# urov_schematic_2.net
KiCad netlist of a schematic drawn in EAGLE
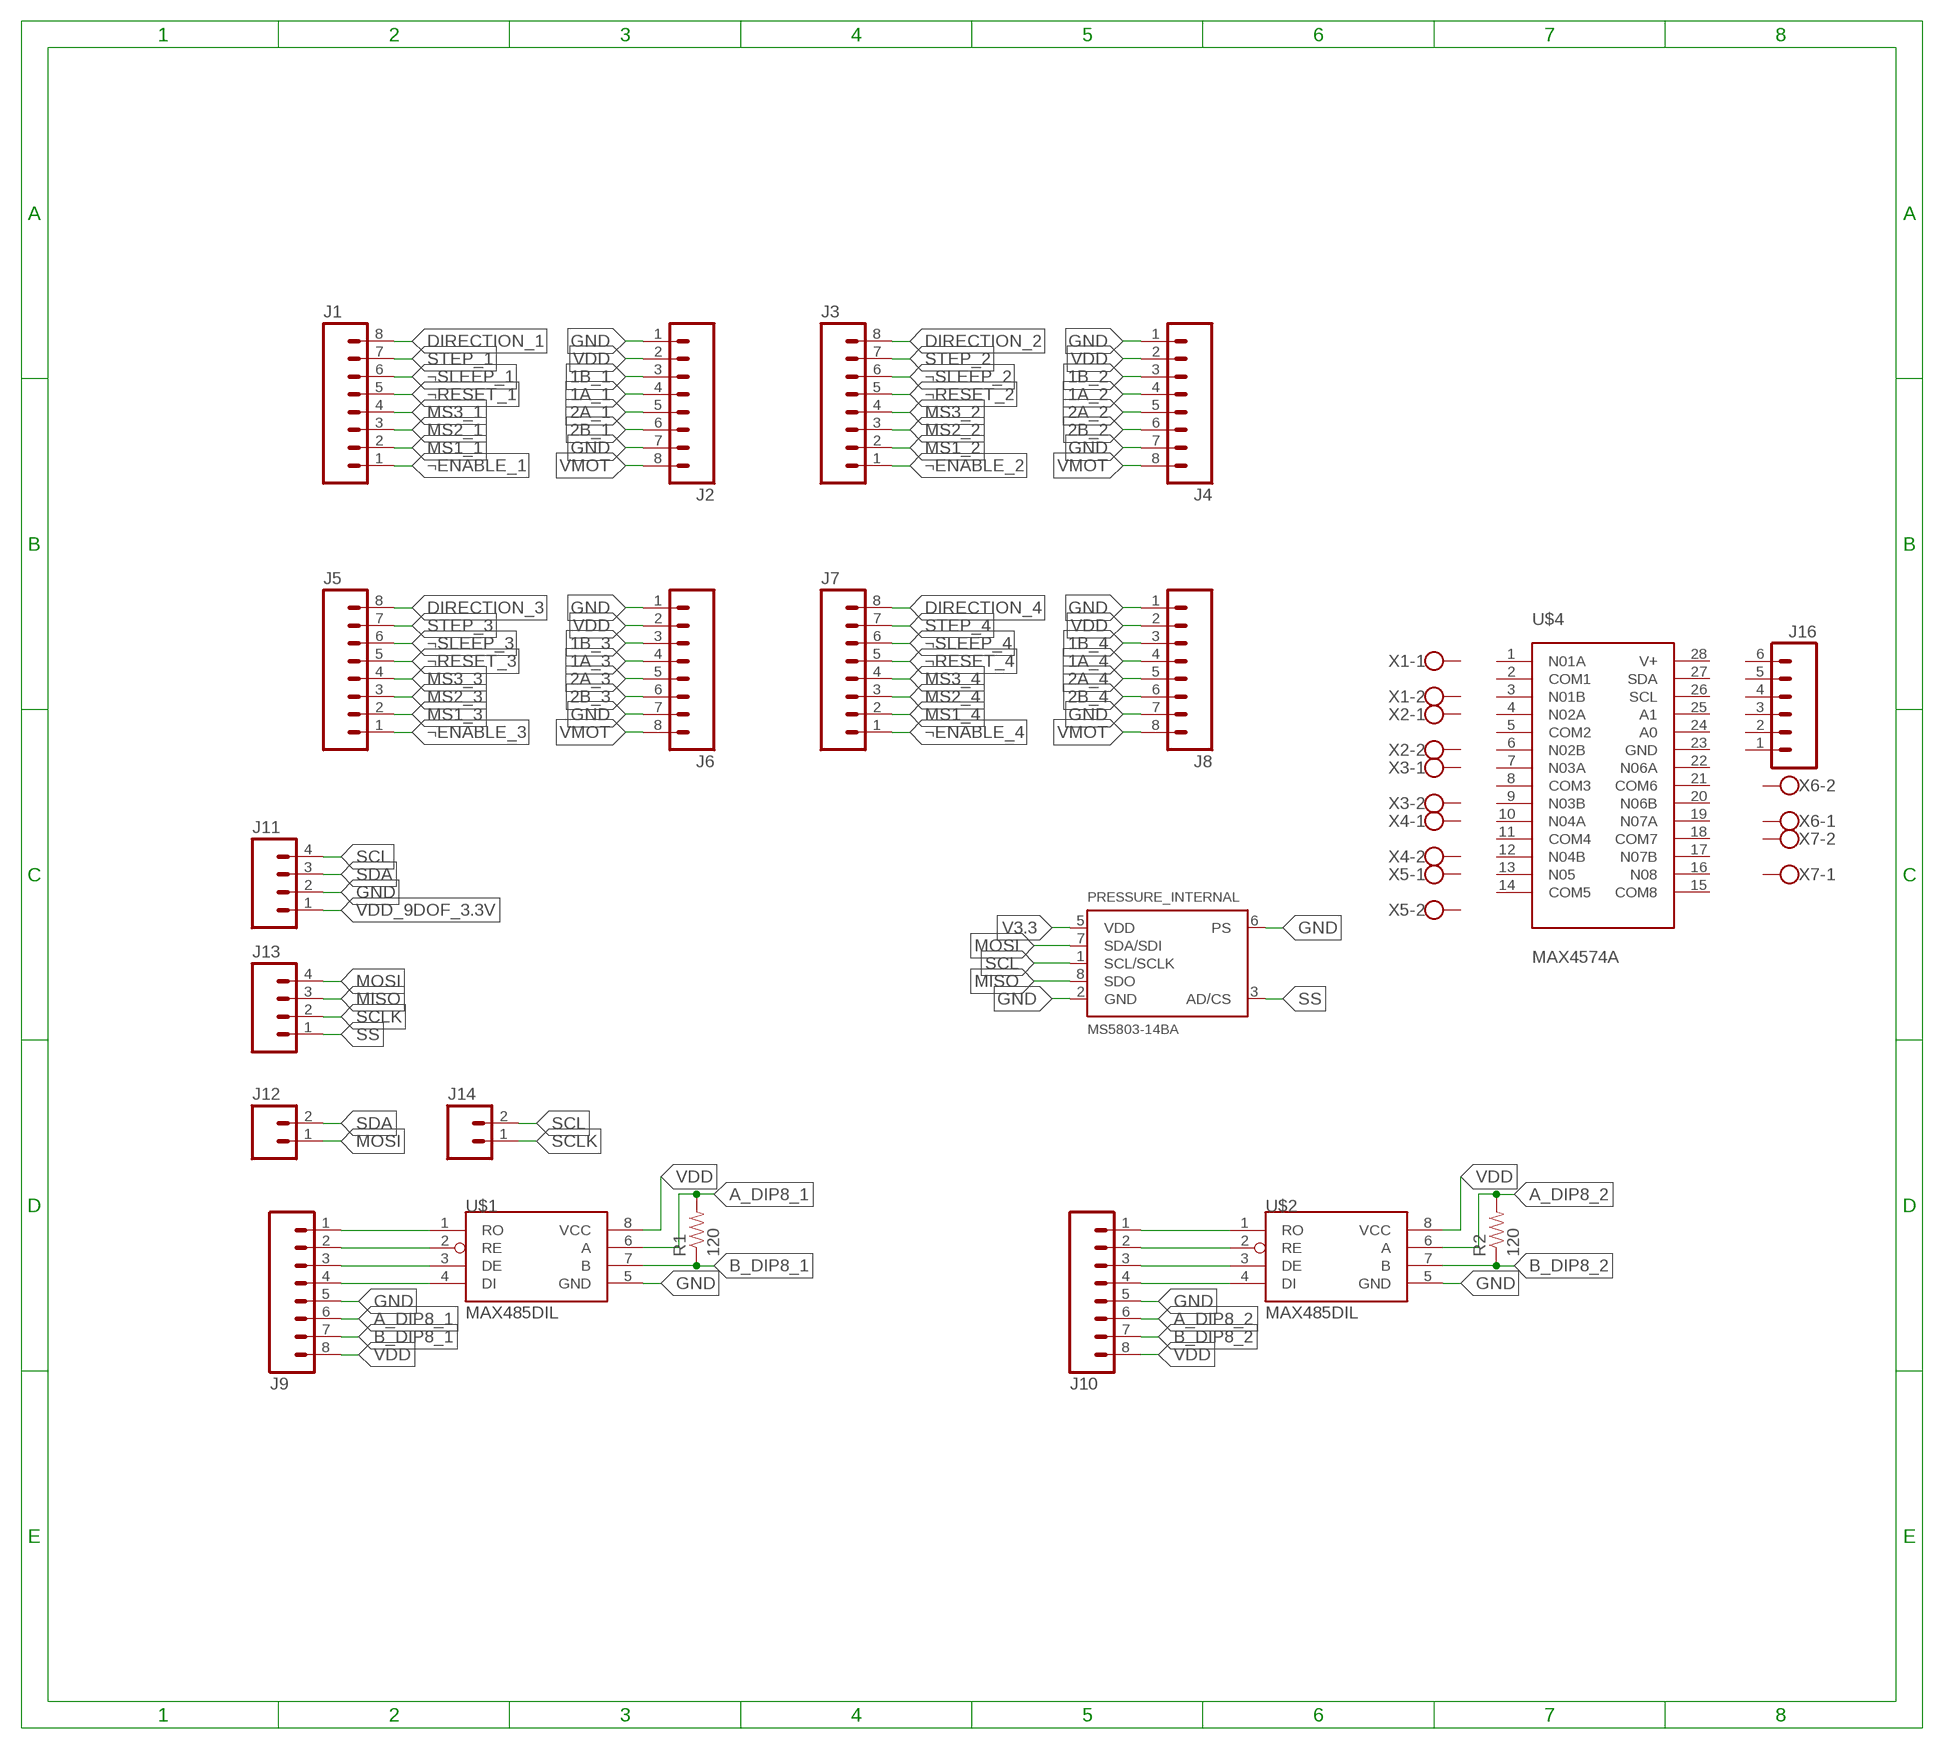
[diagram p0: schematic, sheet 1]

(export (version "E")
  (design (tool "Eeschema 10.0.6"))
  (components
    (comp (ref "J1")
      (value "M08")
      (footprint "eagle-import:1X08_ROUND")
      (libsource (lib "eagle-import") (part "M08"))
    )
    (comp (ref "J2")
      (value "M08")
      (footprint "eagle-import:1X08_ROUND")
      (libsource (lib "eagle-import") (part "M08"))
    )
    (comp (ref "J3")
      (value "M08")
      (footprint "eagle-import:1X08_ROUND")
      (libsource (lib "eagle-import") (part "M08"))
    )
    (comp (ref "J4")
      (value "M08")
      (footprint "eagle-import:1X08_ROUND")
      (libsource (lib "eagle-import") (part "M08"))
    )
    (comp (ref "J5")
      (value "M08")
      (footprint "eagle-import:1X08_ROUND")
      (libsource (lib "eagle-import") (part "M08"))
    )
    (comp (ref "J6")
      (value "M08")
      (footprint "eagle-import:1X08_ROUND")
      (libsource (lib "eagle-import") (part "M08"))
    )
    (comp (ref "J7")
      (value "M08")
      (footprint "eagle-import:1X08_ROUND")
      (libsource (lib "eagle-import") (part "M08"))
    )
    (comp (ref "J8")
      (value "M08")
      (footprint "eagle-import:1X08_ROUND")
      (libsource (lib "eagle-import") (part "M08"))
    )
    (comp (ref "J9")
      (value "M08")
      (footprint "eagle-import:1X08_ROUND")
      (libsource (lib "eagle-import") (part "M08"))
    )
    (comp (ref "J10")
      (value "M08")
      (footprint "eagle-import:1X08_ROUND")
      (libsource (lib "eagle-import") (part "M08"))
    )
    (comp (ref "J11")
      (value "M04PTH")
      (footprint "eagle-import:1X04")
      (libsource (lib "eagle-import") (part "M04PTH"))
    )
    (comp (ref "J12")
      (value "M02PTH")
      (footprint "eagle-import:1X02")
      (libsource (lib "eagle-import") (part "M02PTH"))
    )
    (comp (ref "J13")
      (value "M04PTH")
      (footprint "eagle-import:1X04")
      (libsource (lib "eagle-import") (part "M04PTH"))
    )
    (comp (ref "J14")
      (value "M02PTH")
      (footprint "eagle-import:1X02")
      (libsource (lib "eagle-import") (part "M02PTH"))
    )
    (comp (ref "J16")
      (value "M06POGOPIN_HOLES_ONLY")
      (footprint "eagle-import:1X06_HOLES_ONLY")
      (libsource (lib "eagle-import") (part "M06POGOPIN_HOLES_ONLY"))
    )
    (comp (ref "PRESSURE_INTERNAL")
      (value "MS5803-14BA")
      (footprint "eagle-import:MS5803")
      (libsource (lib "eagle-import") (part "MS5803-14BA"))
    )
    (comp (ref "R1")
      (value "120")
      (footprint "eagle-import:0805")
      (libsource (lib "eagle-import") (part "RESISTOR0805-RES"))
    )
    (comp (ref "R2")
      (value "120")
      (footprint "eagle-import:0805")
      (libsource (lib "eagle-import") (part "RESISTOR0805-RES"))
    )
    (comp (ref "U$1")
      (value "MAX485DIL")
      (footprint "eagle-import:DIL08")
      (libsource (lib "eagle-import") (part "MAX485DIL"))
    )
    (comp (ref "U$2")
      (value "MAX485DIL")
      (footprint "eagle-import:DIL08")
      (libsource (lib "eagle-import") (part "MAX485DIL"))
    )
    (comp (ref "U$4")
      (value "MAX4574A")
      (footprint "eagle-import:28-SSOP")
      (libsource (lib "eagle-import") (part "MAX4574A"))
    )
    (comp (ref "X1")
      (value "W237-102")
      (footprint "eagle-import:W237-102")
      (fields (field (name "MPN") "237-102"))
      (libsource (lib "eagle-import") (part "W237-102"))
    )
    (comp (ref "X2")
      (value "W237-102")
      (footprint "eagle-import:W237-102")
      (fields (field (name "MPN") "237-102"))
      (libsource (lib "eagle-import") (part "W237-102"))
    )
    (comp (ref "X3")
      (value "W237-102")
      (footprint "eagle-import:W237-102")
      (fields (field (name "MPN") "237-102"))
      (libsource (lib "eagle-import") (part "W237-102"))
    )
    (comp (ref "X4")
      (value "W237-102")
      (footprint "eagle-import:W237-102")
      (fields (field (name "MPN") "237-102"))
      (libsource (lib "eagle-import") (part "W237-102"))
    )
    (comp (ref "X5")
      (value "W237-102")
      (footprint "eagle-import:W237-102")
      (fields (field (name "MPN") "237-102"))
      (libsource (lib "eagle-import") (part "W237-102"))
    )
    (comp (ref "X6")
      (value "W237-102")
      (footprint "eagle-import:W237-102")
      (fields (field (name "MPN") "237-102"))
      (libsource (lib "eagle-import") (part "W237-102"))
    )
    (comp (ref "X7")
      (value "W237-102")
      (footprint "eagle-import:W237-102")
      (fields (field (name "MPN") "237-102"))
      (libsource (lib "eagle-import") (part "W237-102"))
    )
  )
  (nets
    (net (code "1") (name "1A_1") (class "Default")
      (node (ref "J2") (pin "4") (pinfunction "4_4") (pintype "passive"))
    )
    (net (code "2") (name "1A_2") (class "Default")
      (node (ref "J4") (pin "4") (pinfunction "4_4") (pintype "passive"))
    )
    (net (code "3") (name "1A_3") (class "Default")
      (node (ref "J6") (pin "4") (pinfunction "4_4") (pintype "passive"))
    )
    (net (code "4") (name "1A_4") (class "Default")
      (node (ref "J8") (pin "4") (pinfunction "4_4") (pintype "passive"))
    )
    (net (code "5") (name "1B_1") (class "Default")
      (node (ref "J2") (pin "3") (pinfunction "3_3") (pintype "passive"))
    )
    (net (code "6") (name "1B_2") (class "Default")
      (node (ref "J4") (pin "3") (pinfunction "3_3") (pintype "passive"))
    )
    (net (code "7") (name "1B_3") (class "Default")
      (node (ref "J6") (pin "3") (pinfunction "3_3") (pintype "passive"))
    )
    (net (code "8") (name "1B_4") (class "Default")
      (node (ref "J8") (pin "3") (pinfunction "3_3") (pintype "passive"))
    )
    (net (code "9") (name "2A_1") (class "Default")
      (node (ref "J2") (pin "5") (pinfunction "5_5") (pintype "passive"))
    )
    (net (code "10") (name "2A_2") (class "Default")
      (node (ref "J4") (pin "5") (pinfunction "5_5") (pintype "passive"))
    )
    (net (code "11") (name "2A_3") (class "Default")
      (node (ref "J6") (pin "5") (pinfunction "5_5") (pintype "passive"))
    )
    (net (code "12") (name "2A_4") (class "Default")
      (node (ref "J8") (pin "5") (pinfunction "5_5") (pintype "passive"))
    )
    (net (code "13") (name "2B_1") (class "Default")
      (node (ref "J2") (pin "6") (pinfunction "6_6") (pintype "passive"))
    )
    (net (code "14") (name "2B_2") (class "Default")
      (node (ref "J4") (pin "6") (pinfunction "6_6") (pintype "passive"))
    )
    (net (code "15") (name "2B_3") (class "Default")
      (node (ref "J6") (pin "6") (pinfunction "6_6") (pintype "passive"))
    )
    (net (code "16") (name "2B_4") (class "Default")
      (node (ref "J8") (pin "6") (pinfunction "6_6") (pintype "passive"))
    )
    (net (code "17") (name "A_DIP8_1") (class "Default")
      (node (ref "J9") (pin "6") (pinfunction "6_6") (pintype "passive"))
      (node (ref "R1") (pin "2") (pinfunction "2_2") (pintype "passive"))
      (node (ref "U$1") (pin "6") (pinfunction "A_6") (pintype "bidirectional"))
    )
    (net (code "18") (name "A_DIP8_2") (class "Default")
      (node (ref "J10") (pin "6") (pinfunction "6_6") (pintype "passive"))
      (node (ref "R2") (pin "2") (pinfunction "2_2") (pintype "passive"))
      (node (ref "U$2") (pin "6") (pinfunction "A_6") (pintype "bidirectional"))
    )
    (net (code "19") (name "B_DIP8_1") (class "Default")
      (node (ref "J9") (pin "7") (pinfunction "7_7") (pintype "passive"))
      (node (ref "R1") (pin "1") (pinfunction "1_1") (pintype "passive"))
      (node (ref "U$1") (pin "7") (pinfunction "B_7") (pintype "bidirectional"))
    )
    (net (code "20") (name "B_DIP8_2") (class "Default")
      (node (ref "J10") (pin "7") (pinfunction "7_7") (pintype "passive"))
      (node (ref "R2") (pin "1") (pinfunction "1_1") (pintype "passive"))
      (node (ref "U$2") (pin "7") (pinfunction "B_7") (pintype "bidirectional"))
    )
    (net (code "21") (name "DIRECTION_1") (class "Default")
      (node (ref "J1") (pin "8") (pinfunction "8_8") (pintype "passive"))
    )
    (net (code "22") (name "DIRECTION_2") (class "Default")
      (node (ref "J3") (pin "8") (pinfunction "8_8") (pintype "passive"))
    )
    (net (code "23") (name "DIRECTION_3") (class "Default")
      (node (ref "J5") (pin "8") (pinfunction "8_8") (pintype "passive"))
    )
    (net (code "24") (name "DIRECTION_4") (class "Default")
      (node (ref "J7") (pin "8") (pinfunction "8_8") (pintype "passive"))
    )
    (net (code "25") (name "GND") (class "Default")
      (node (ref "J10") (pin "5") (pinfunction "5_5") (pintype "passive"))
      (node (ref "J11") (pin "2") (pinfunction "2_2") (pintype "passive"))
      (node (ref "J2") (pin "1") (pinfunction "1_1") (pintype "passive"))
      (node (ref "J2") (pin "7") (pinfunction "7_7") (pintype "passive"))
      (node (ref "J4") (pin "1") (pinfunction "1_1") (pintype "passive"))
      (node (ref "J4") (pin "7") (pinfunction "7_7") (pintype "passive"))
      (node (ref "J6") (pin "1") (pinfunction "1_1") (pintype "passive"))
      (node (ref "J6") (pin "7") (pinfunction "7_7") (pintype "passive"))
      (node (ref "J8") (pin "1") (pinfunction "1_1") (pintype "passive"))
      (node (ref "J8") (pin "7") (pinfunction "7_7") (pintype "passive"))
      (node (ref "J9") (pin "5") (pinfunction "5_5") (pintype "passive"))
      (node (ref "PRESSURE_INTERNAL") (pin "2") (pinfunction "GND_2") (pintype "bidirectional"))
      (node (ref "PRESSURE_INTERNAL") (pin "6") (pinfunction "PS_6") (pintype "bidirectional"))
      (node (ref "U$1") (pin "5") (pinfunction "GND_5") (pintype "bidirectional"))
      (node (ref "U$2") (pin "5") (pinfunction "GND_5") (pintype "bidirectional"))
    )
    (net (code "26") (name "MISO") (class "Default")
      (node (ref "J13") (pin "3") (pinfunction "3_3") (pintype "passive"))
      (node (ref "PRESSURE_INTERNAL") (pin "8") (pinfunction "SDO_8") (pintype "bidirectional"))
    )
    (net (code "27") (name "MOSI") (class "Default")
      (node (ref "J12") (pin "1") (pinfunction "1_1") (pintype "passive"))
      (node (ref "J13") (pin "4") (pinfunction "4_4") (pintype "passive"))
      (node (ref "PRESSURE_INTERNAL") (pin "7") (pinfunction "SDA/SDI_7") (pintype "bidirectional"))
    )
    (net (code "28") (name "MS1_1") (class "Default")
      (node (ref "J1") (pin "2") (pinfunction "2_2") (pintype "passive"))
    )
    (net (code "29") (name "MS1_2") (class "Default")
      (node (ref "J3") (pin "2") (pinfunction "2_2") (pintype "passive"))
    )
    (net (code "30") (name "MS1_3") (class "Default")
      (node (ref "J5") (pin "2") (pinfunction "2_2") (pintype "passive"))
    )
    (net (code "31") (name "MS1_4") (class "Default")
      (node (ref "J7") (pin "2") (pinfunction "2_2") (pintype "passive"))
    )
    (net (code "32") (name "MS2_1") (class "Default")
      (node (ref "J1") (pin "3") (pinfunction "3_3") (pintype "passive"))
    )
    (net (code "33") (name "MS2_2") (class "Default")
      (node (ref "J3") (pin "3") (pinfunction "3_3") (pintype "passive"))
    )
    (net (code "34") (name "MS2_3") (class "Default")
      (node (ref "J5") (pin "3") (pinfunction "3_3") (pintype "passive"))
    )
    (net (code "35") (name "MS2_4") (class "Default")
      (node (ref "J7") (pin "3") (pinfunction "3_3") (pintype "passive"))
    )
    (net (code "36") (name "MS3_1") (class "Default")
      (node (ref "J1") (pin "4") (pinfunction "4_4") (pintype "passive"))
    )
    (net (code "37") (name "MS3_2") (class "Default")
      (node (ref "J3") (pin "4") (pinfunction "4_4") (pintype "passive"))
    )
    (net (code "38") (name "MS3_3") (class "Default")
      (node (ref "J5") (pin "4") (pinfunction "4_4") (pintype "passive"))
    )
    (net (code "39") (name "MS3_4") (class "Default")
      (node (ref "J7") (pin "4") (pinfunction "4_4") (pintype "passive"))
    )
    (net (code "40") (name "Net-(U$1-DE)") (class "Default")
      (node (ref "J9") (pin "3") (pinfunction "3_3") (pintype "passive"))
      (node (ref "U$1") (pin "3") (pinfunction "DE_3") (pintype "bidirectional"))
    )
    (net (code "41") (name "Net-(U$1-DI)") (class "Default")
      (node (ref "J9") (pin "4") (pinfunction "4_4") (pintype "passive"))
      (node (ref "U$1") (pin "4") (pinfunction "DI_4") (pintype "bidirectional"))
    )
    (net (code "42") (name "Net-(U$1-RE)") (class "Default")
      (node (ref "J9") (pin "2") (pinfunction "2_2") (pintype "passive"))
      (node (ref "U$1") (pin "2") (pinfunction "RE_2") (pintype "bidirectional"))
    )
    (net (code "43") (name "Net-(U$1-RO)") (class "Default")
      (node (ref "J9") (pin "1") (pinfunction "1_1") (pintype "passive"))
      (node (ref "U$1") (pin "1") (pinfunction "RO_1") (pintype "bidirectional"))
    )
    (net (code "44") (name "Net-(U$2-DE)") (class "Default")
      (node (ref "J10") (pin "3") (pinfunction "3_3") (pintype "passive"))
      (node (ref "U$2") (pin "3") (pinfunction "DE_3") (pintype "bidirectional"))
    )
    (net (code "45") (name "Net-(U$2-DI)") (class "Default")
      (node (ref "J10") (pin "4") (pinfunction "4_4") (pintype "passive"))
      (node (ref "U$2") (pin "4") (pinfunction "DI_4") (pintype "bidirectional"))
    )
    (net (code "46") (name "Net-(U$2-RE)") (class "Default")
      (node (ref "J10") (pin "2") (pinfunction "2_2") (pintype "passive"))
      (node (ref "U$2") (pin "2") (pinfunction "RE_2") (pintype "bidirectional"))
    )
    (net (code "47") (name "Net-(U$2-RO)") (class "Default")
      (node (ref "J10") (pin "1") (pinfunction "1_1") (pintype "passive"))
      (node (ref "U$2") (pin "1") (pinfunction "RO_1") (pintype "bidirectional"))
    )
    (net (code "48") (name "SCL") (class "Default")
      (node (ref "J11") (pin "4") (pinfunction "4_4") (pintype "passive"))
      (node (ref "J14") (pin "2") (pinfunction "2_2") (pintype "passive"))
      (node (ref "PRESSURE_INTERNAL") (pin "1") (pinfunction "SCL/SCLK_1") (pintype "bidirectional"))
    )
    (net (code "49") (name "SCLK") (class "Default")
      (node (ref "J13") (pin "2") (pinfunction "2_2") (pintype "passive"))
      (node (ref "J14") (pin "1") (pinfunction "1_1") (pintype "passive"))
    )
    (net (code "50") (name "SDA") (class "Default")
      (node (ref "J11") (pin "3") (pinfunction "3_3") (pintype "passive"))
      (node (ref "J12") (pin "2") (pinfunction "2_2") (pintype "passive"))
    )
    (net (code "51") (name "SS") (class "Default")
      (node (ref "J13") (pin "1") (pinfunction "1_1") (pintype "passive"))
      (node (ref "PRESSURE_INTERNAL") (pin "3") (pinfunction "AD/CS_3") (pintype "bidirectional"))
    )
    (net (code "52") (name "STEP_1") (class "Default")
      (node (ref "J1") (pin "7") (pinfunction "7_7") (pintype "passive"))
    )
    (net (code "53") (name "STEP_2") (class "Default")
      (node (ref "J3") (pin "7") (pinfunction "7_7") (pintype "passive"))
    )
    (net (code "54") (name "STEP_3") (class "Default")
      (node (ref "J5") (pin "7") (pinfunction "7_7") (pintype "passive"))
    )
    (net (code "55") (name "STEP_4") (class "Default")
      (node (ref "J7") (pin "7") (pinfunction "7_7") (pintype "passive"))
    )
    (net (code "56") (name "V3.3") (class "Default")
      (node (ref "PRESSURE_INTERNAL") (pin "5") (pinfunction "VDD_5") (pintype "bidirectional"))
    )
    (net (code "57") (name "VDD") (class "Default")
      (node (ref "J10") (pin "8") (pinfunction "8_8") (pintype "passive"))
      (node (ref "J2") (pin "2") (pinfunction "2_2") (pintype "passive"))
      (node (ref "J4") (pin "2") (pinfunction "2_2") (pintype "passive"))
      (node (ref "J6") (pin "2") (pinfunction "2_2") (pintype "passive"))
      (node (ref "J8") (pin "2") (pinfunction "2_2") (pintype "passive"))
      (node (ref "J9") (pin "8") (pinfunction "8_8") (pintype "passive"))
      (node (ref "U$1") (pin "8") (pinfunction "VCC_8") (pintype "bidirectional"))
      (node (ref "U$2") (pin "8") (pinfunction "VCC_8") (pintype "bidirectional"))
    )
    (net (code "58") (name "VDD_9DOF_3.3V") (class "Default")
      (node (ref "J11") (pin "1") (pinfunction "1_1") (pintype "passive"))
    )
    (net (code "59") (name "VMOT") (class "Default")
      (node (ref "J2") (pin "8") (pinfunction "8_8") (pintype "passive"))
      (node (ref "J4") (pin "8") (pinfunction "8_8") (pintype "passive"))
      (node (ref "J6") (pin "8") (pinfunction "8_8") (pintype "passive"))
      (node (ref "J8") (pin "8") (pinfunction "8_8") (pintype "passive"))
    )
    (net (code "60") (name "unconnected-(J16-Pad1)") (class "Default")
      (node (ref "J16") (pin "1") (pinfunction "1_1") (pintype "passive"))
    )
    (net (code "61") (name "unconnected-(J16-Pad2)") (class "Default")
      (node (ref "J16") (pin "2") (pinfunction "2_2") (pintype "passive"))
    )
    (net (code "62") (name "unconnected-(J16-Pad3)") (class "Default")
      (node (ref "J16") (pin "3") (pinfunction "3_3") (pintype "passive"))
    )
    (net (code "63") (name "unconnected-(J16-Pad4)") (class "Default")
      (node (ref "J16") (pin "4") (pinfunction "4_4") (pintype "passive"))
    )
    (net (code "64") (name "unconnected-(J16-Pad5)") (class "Default")
      (node (ref "J16") (pin "5") (pinfunction "5_5") (pintype "passive"))
    )
    (net (code "65") (name "unconnected-(J16-Pad6)") (class "Default")
      (node (ref "J16") (pin "6") (pinfunction "6_6") (pintype "passive"))
    )
    (net (code "66") (name "unconnected-(U$4-A0-Pad24)") (class "Default")
      (node (ref "U$4") (pin "24") (pinfunction "A0_24") (pintype "bidirectional"))
    )
    (net (code "67") (name "unconnected-(U$4-A1-Pad25)") (class "Default")
      (node (ref "U$4") (pin "25") (pinfunction "A1_25") (pintype "bidirectional"))
    )
    (net (code "68") (name "unconnected-(U$4-COM1-Pad2)") (class "Default")
      (node (ref "U$4") (pin "2") (pinfunction "COM1_2") (pintype "bidirectional"))
    )
    (net (code "69") (name "unconnected-(U$4-COM2-Pad5)") (class "Default")
      (node (ref "U$4") (pin "5") (pinfunction "COM2_5") (pintype "bidirectional"))
    )
    (net (code "70") (name "unconnected-(U$4-COM3-Pad8)") (class "Default")
      (node (ref "U$4") (pin "8") (pinfunction "COM3_8") (pintype "bidirectional"))
    )
    (net (code "71") (name "unconnected-(U$4-COM4-Pad11)") (class "Default")
      (node (ref "U$4") (pin "11") (pinfunction "COM4_11") (pintype "bidirectional"))
    )
    (net (code "72") (name "unconnected-(U$4-COM5-Pad14)") (class "Default")
      (node (ref "U$4") (pin "14") (pinfunction "COM5_14") (pintype "bidirectional"))
    )
    (net (code "73") (name "unconnected-(U$4-COM6-Pad21)") (class "Default")
      (node (ref "U$4") (pin "21") (pinfunction "COM6_21") (pintype "bidirectional"))
    )
    (net (code "74") (name "unconnected-(U$4-COM7-Pad18)") (class "Default")
      (node (ref "U$4") (pin "18") (pinfunction "COM7_18") (pintype "bidirectional"))
    )
    (net (code "75") (name "unconnected-(U$4-COM8-Pad15)") (class "Default")
      (node (ref "U$4") (pin "15") (pinfunction "COM8_15") (pintype "bidirectional"))
    )
    (net (code "76") (name "unconnected-(U$4-GND-Pad23)") (class "Default")
      (node (ref "U$4") (pin "23") (pinfunction "GND_23") (pintype "bidirectional"))
    )
    (net (code "77") (name "unconnected-(U$4-N01A-Pad1)") (class "Default")
      (node (ref "U$4") (pin "1") (pinfunction "N01A_1") (pintype "bidirectional"))
    )
    (net (code "78") (name "unconnected-(U$4-N01B-Pad3)") (class "Default")
      (node (ref "U$4") (pin "3") (pinfunction "N01B_3") (pintype "bidirectional"))
    )
    (net (code "79") (name "unconnected-(U$4-N02A-Pad4)") (class "Default")
      (node (ref "U$4") (pin "4") (pinfunction "N02A_4") (pintype "bidirectional"))
    )
    (net (code "80") (name "unconnected-(U$4-N02B-Pad6)") (class "Default")
      (node (ref "U$4") (pin "6") (pinfunction "N02B_6") (pintype "bidirectional"))
    )
    (net (code "81") (name "unconnected-(U$4-N03A-Pad7)") (class "Default")
      (node (ref "U$4") (pin "7") (pinfunction "N03A_7") (pintype "bidirectional"))
    )
    (net (code "82") (name "unconnected-(U$4-N03B-Pad9)") (class "Default")
      (node (ref "U$4") (pin "9") (pinfunction "N03B_9") (pintype "bidirectional"))
    )
    (net (code "83") (name "unconnected-(U$4-N04A-Pad10)") (class "Default")
      (node (ref "U$4") (pin "10") (pinfunction "N04A_10") (pintype "bidirectional"))
    )
    (net (code "84") (name "unconnected-(U$4-N04B-Pad12)") (class "Default")
      (node (ref "U$4") (pin "12") (pinfunction "N04B_12") (pintype "bidirectional"))
    )
    (net (code "85") (name "unconnected-(U$4-N05-Pad13)") (class "Default")
      (node (ref "U$4") (pin "13") (pinfunction "N05_13") (pintype "bidirectional"))
    )
    (net (code "86") (name "unconnected-(U$4-N06A-Pad22)") (class "Default")
      (node (ref "U$4") (pin "22") (pinfunction "N06A_22") (pintype "bidirectional"))
    )
    (net (code "87") (name "unconnected-(U$4-N06B-Pad20)") (class "Default")
      (node (ref "U$4") (pin "20") (pinfunction "N06B_20") (pintype "bidirectional"))
    )
    (net (code "88") (name "unconnected-(U$4-N07A-Pad19)") (class "Default")
      (node (ref "U$4") (pin "19") (pinfunction "N07A_19") (pintype "bidirectional"))
    )
    (net (code "89") (name "unconnected-(U$4-N07B-Pad17)") (class "Default")
      (node (ref "U$4") (pin "17") (pinfunction "N07B_17") (pintype "bidirectional"))
    )
    (net (code "90") (name "unconnected-(U$4-N08-Pad16)") (class "Default")
      (node (ref "U$4") (pin "16") (pinfunction "N08_16") (pintype "bidirectional"))
    )
    (net (code "91") (name "unconnected-(U$4-SCL-Pad26)") (class "Default")
      (node (ref "U$4") (pin "26") (pinfunction "SCL_26") (pintype "bidirectional"))
    )
    (net (code "92") (name "unconnected-(U$4-SDA-Pad27)") (class "Default")
      (node (ref "U$4") (pin "27") (pinfunction "SDA_27") (pintype "bidirectional"))
    )
    (net (code "93") (name "unconnected-(U$4-V+-Pad28)") (class "Default")
      (node (ref "U$4") (pin "28") (pinfunction "V+_28") (pintype "bidirectional"))
    )
    (net (code "94") (name "unconnected-(X1A-KL-Pad1)") (class "Default")
      (node (ref "X1") (pin "1") (pinfunction "KL_1") (pintype "passive"))
    )
    (net (code "95") (name "unconnected-(X1B-KL-Pad2)") (class "Default")
      (node (ref "X1") (pin "2") (pinfunction "KL_2") (pintype "passive"))
    )
    (net (code "96") (name "unconnected-(X2A-KL-Pad1)") (class "Default")
      (node (ref "X2") (pin "1") (pinfunction "KL_1") (pintype "passive"))
    )
    (net (code "97") (name "unconnected-(X2B-KL-Pad2)") (class "Default")
      (node (ref "X2") (pin "2") (pinfunction "KL_2") (pintype "passive"))
    )
    (net (code "98") (name "unconnected-(X3A-KL-Pad1)") (class "Default")
      (node (ref "X3") (pin "1") (pinfunction "KL_1") (pintype "passive"))
    )
    (net (code "99") (name "unconnected-(X3B-KL-Pad2)") (class "Default")
      (node (ref "X3") (pin "2") (pinfunction "KL_2") (pintype "passive"))
    )
    (net (code "100") (name "unconnected-(X4A-KL-Pad1)") (class "Default")
      (node (ref "X4") (pin "1") (pinfunction "KL_1") (pintype "passive"))
    )
    (net (code "101") (name "unconnected-(X4B-KL-Pad2)") (class "Default")
      (node (ref "X4") (pin "2") (pinfunction "KL_2") (pintype "passive"))
    )
    (net (code "102") (name "unconnected-(X5A-KL-Pad1)") (class "Default")
      (node (ref "X5") (pin "1") (pinfunction "KL_1") (pintype "passive"))
    )
    (net (code "103") (name "unconnected-(X5B-KL-Pad2)") (class "Default")
      (node (ref "X5") (pin "2") (pinfunction "KL_2") (pintype "passive"))
    )
    (net (code "104") (name "unconnected-(X6A-KL-Pad1)") (class "Default")
      (node (ref "X6") (pin "1") (pinfunction "KL_1") (pintype "passive"))
    )
    (net (code "105") (name "unconnected-(X6B-KL-Pad2)") (class "Default")
      (node (ref "X6") (pin "2") (pinfunction "KL_2") (pintype "passive"))
    )
    (net (code "106") (name "unconnected-(X7A-KL-Pad1)") (class "Default")
      (node (ref "X7") (pin "1") (pinfunction "KL_1") (pintype "passive"))
    )
    (net (code "107") (name "unconnected-(X7B-KL-Pad2)") (class "Default")
      (node (ref "X7") (pin "2") (pinfunction "KL_2") (pintype "passive"))
    )
    (net (code "108") (name "¬ENABLE_1") (class "Default")
      (node (ref "J1") (pin "1") (pinfunction "1_1") (pintype "passive"))
    )
    (net (code "109") (name "¬ENABLE_2") (class "Default")
      (node (ref "J3") (pin "1") (pinfunction "1_1") (pintype "passive"))
    )
    (net (code "110") (name "¬ENABLE_3") (class "Default")
      (node (ref "J5") (pin "1") (pinfunction "1_1") (pintype "passive"))
    )
    (net (code "111") (name "¬ENABLE_4") (class "Default")
      (node (ref "J7") (pin "1") (pinfunction "1_1") (pintype "passive"))
    )
    (net (code "112") (name "¬RESET_1") (class "Default")
      (node (ref "J1") (pin "5") (pinfunction "5_5") (pintype "passive"))
    )
    (net (code "113") (name "¬RESET_2") (class "Default")
      (node (ref "J3") (pin "5") (pinfunction "5_5") (pintype "passive"))
    )
    (net (code "114") (name "¬RESET_3") (class "Default")
      (node (ref "J5") (pin "5") (pinfunction "5_5") (pintype "passive"))
    )
    (net (code "115") (name "¬RESET_4") (class "Default")
      (node (ref "J7") (pin "5") (pinfunction "5_5") (pintype "passive"))
    )
    (net (code "116") (name "¬SLEEP_1") (class "Default")
      (node (ref "J1") (pin "6") (pinfunction "6_6") (pintype "passive"))
    )
    (net (code "117") (name "¬SLEEP_2") (class "Default")
      (node (ref "J3") (pin "6") (pinfunction "6_6") (pintype "passive"))
    )
    (net (code "118") (name "¬SLEEP_3") (class "Default")
      (node (ref "J5") (pin "6") (pinfunction "6_6") (pintype "passive"))
    )
    (net (code "119") (name "¬SLEEP_4") (class "Default")
      (node (ref "J7") (pin "6") (pinfunction "6_6") (pintype "passive"))
    )
  )
)
